# Charger_Board.net
KiCad netlist of a schematic drawn in EAGLE
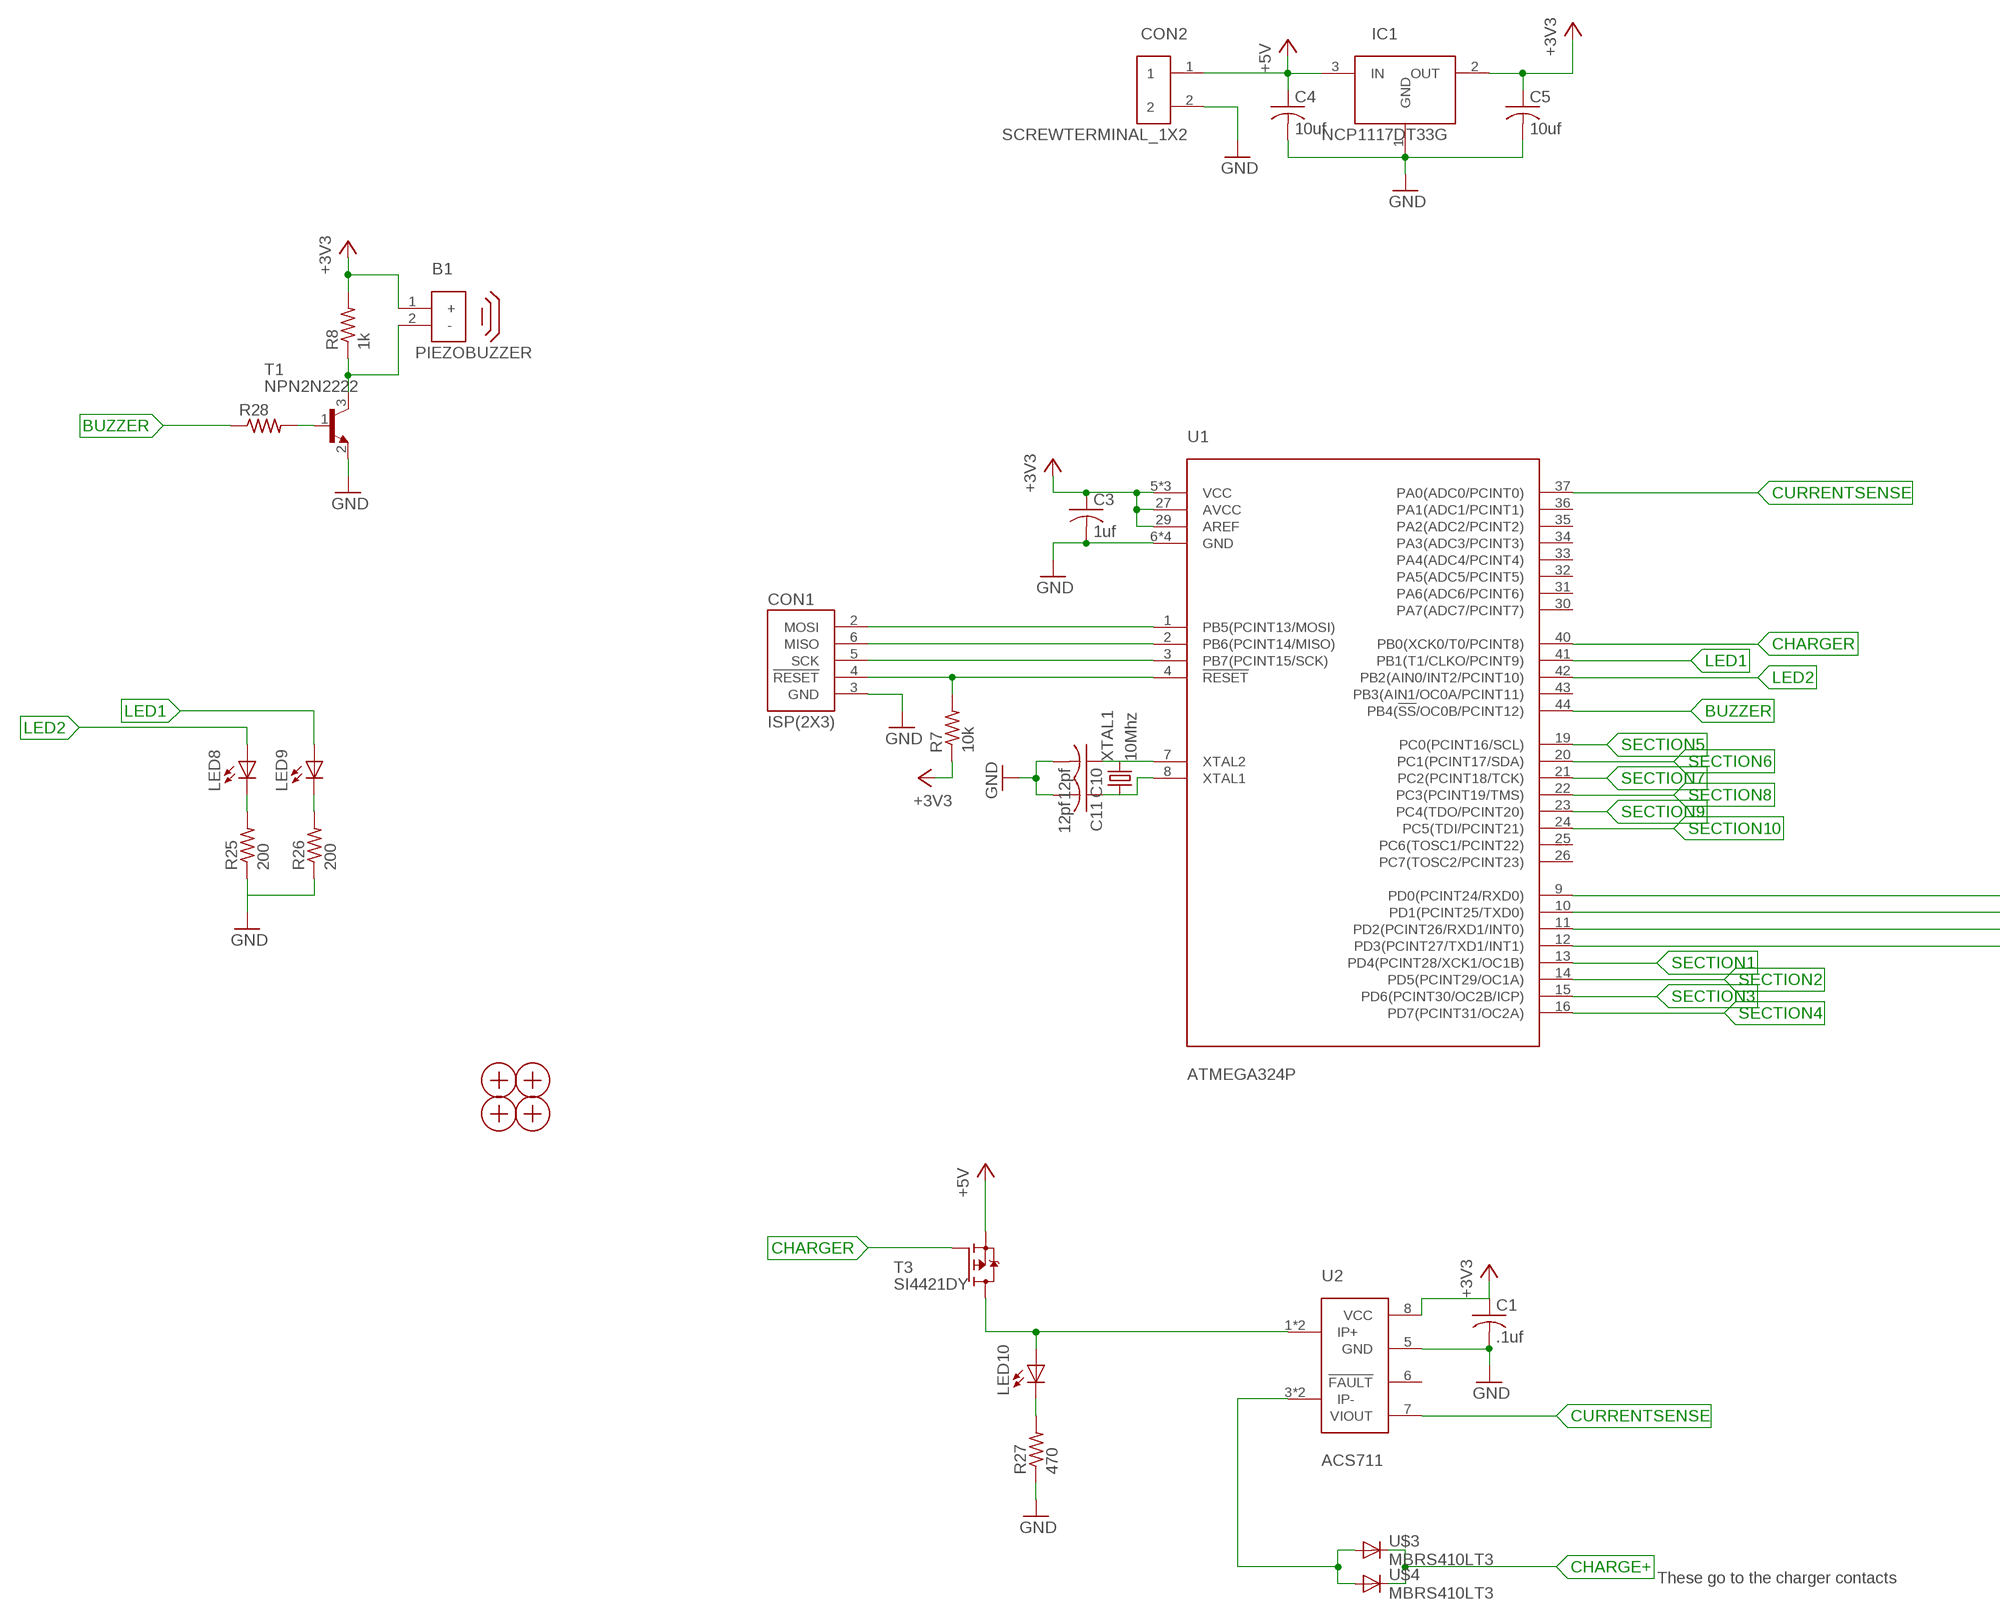
[diagram p0: schematic, sheet 1, part 1 of 2]
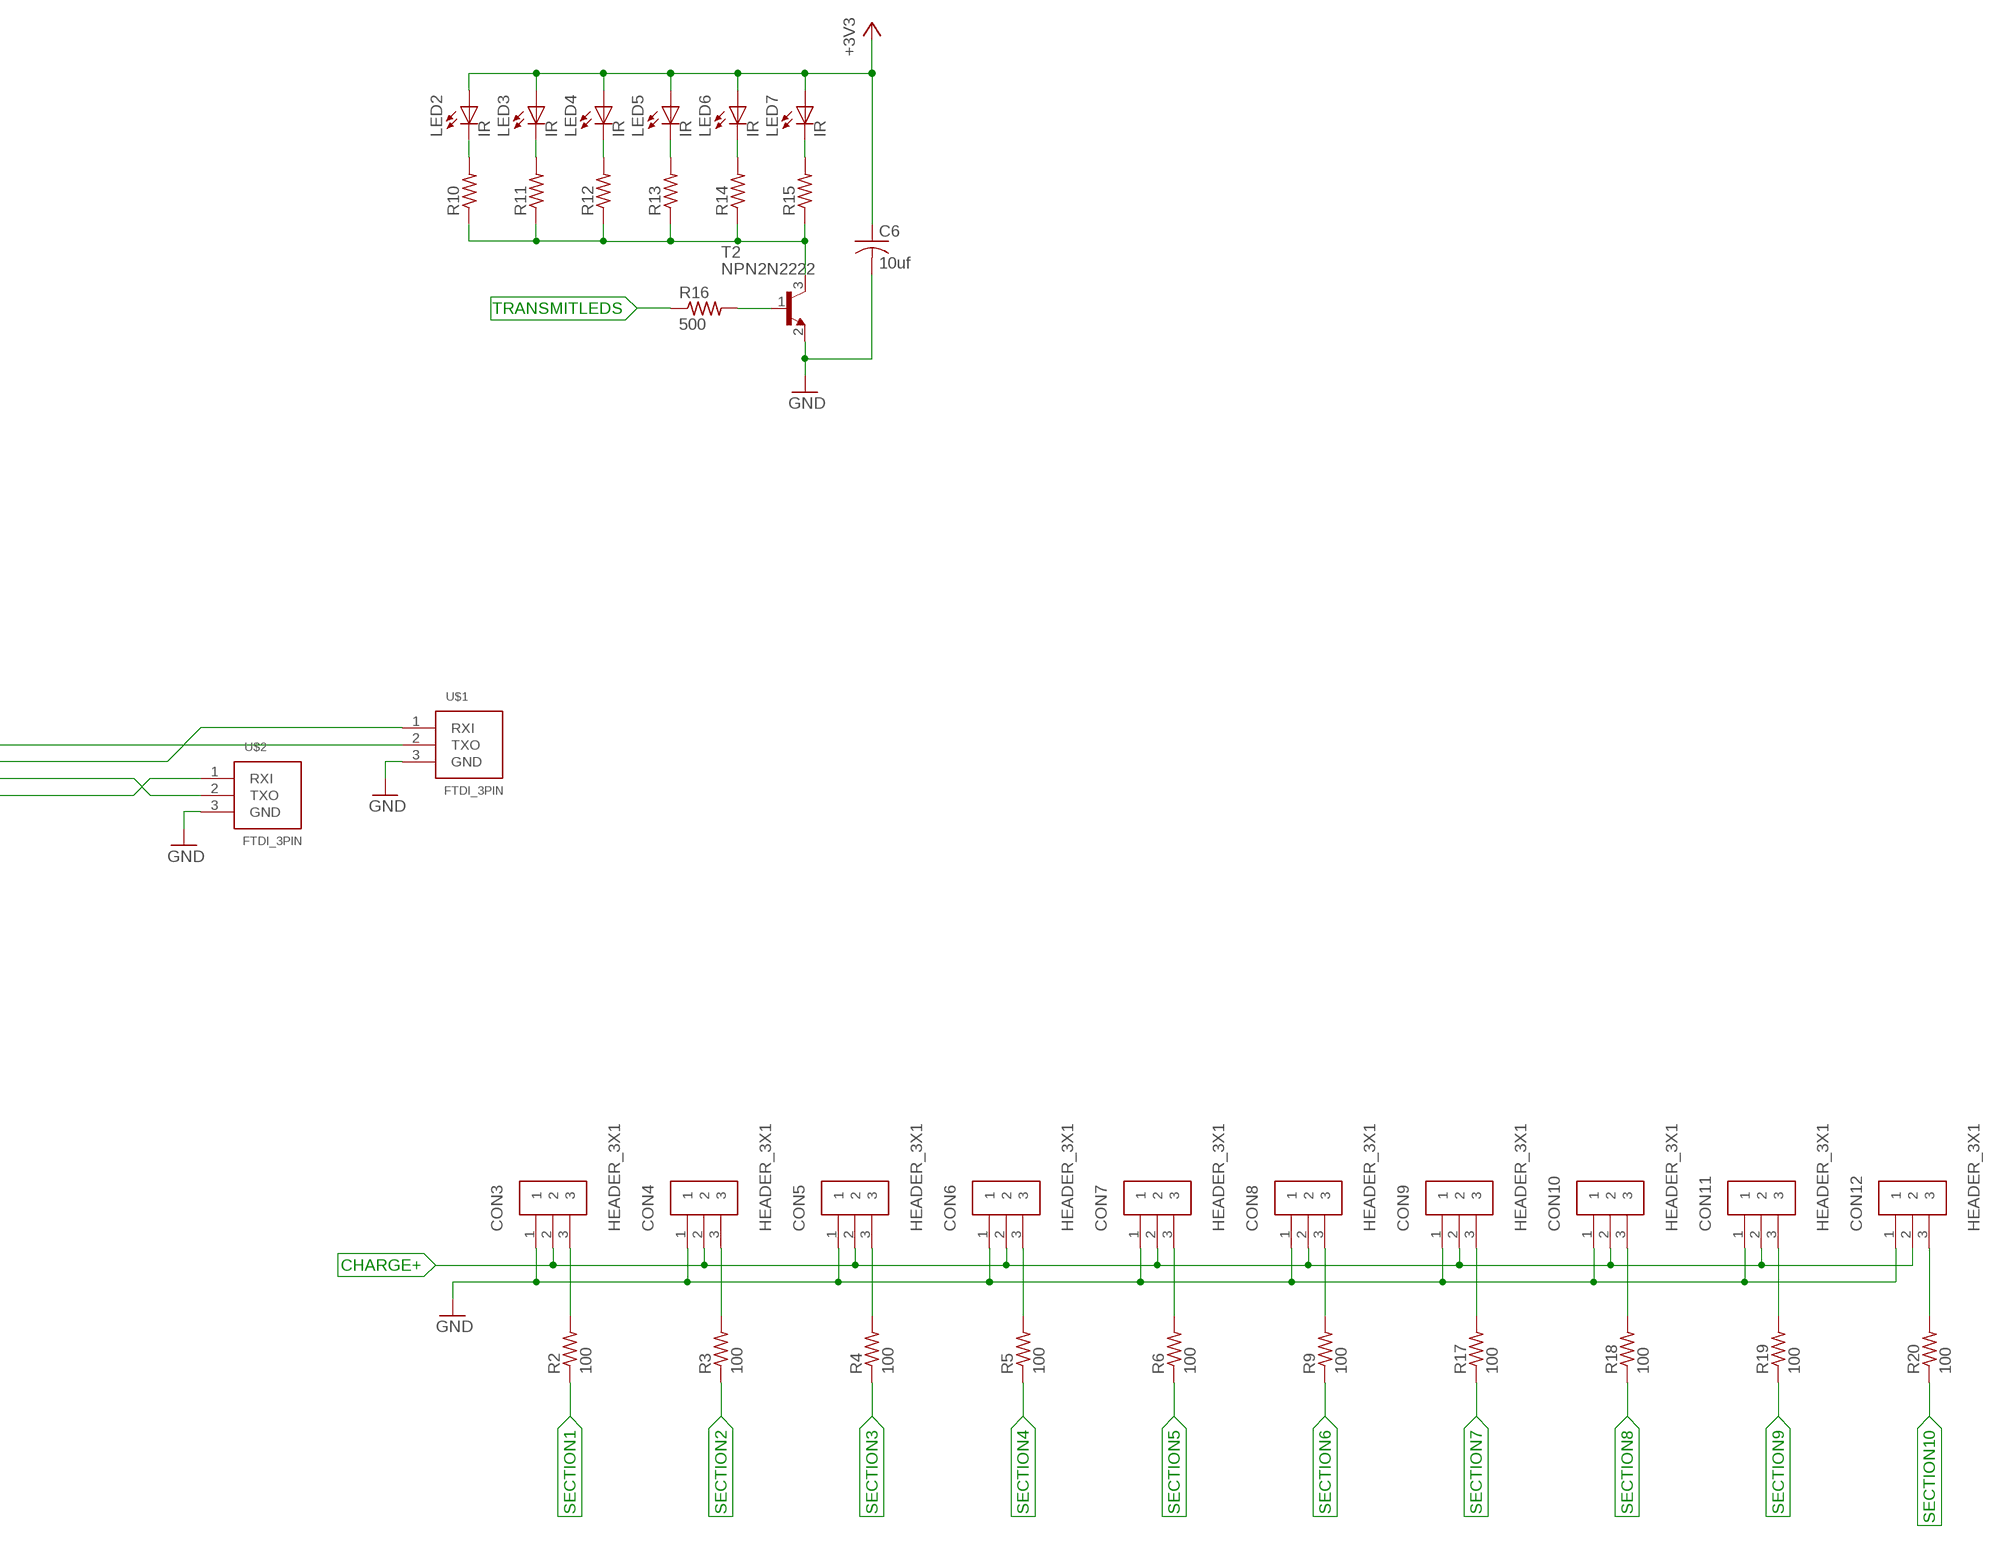
[diagram p1: schematic, sheet 1, part 2 of 2]

(export (version "E")
  (design (tool "Eeschema 10.0.6"))
  (components
    (comp (ref "B1")
      (value "PIEZOBUZZER")
      (footprint "eagle-import:PIEZOBUZZER")
      (libsource (lib "eagle-import") (part "PIEZOBUZZER"))
    )
    (comp (ref "C1")
      (value ".1uf")
      (footprint "eagle-import:0603")
      (libsource (lib "eagle-import") (part "CAP0603"))
    )
    (comp (ref "C3")
      (value "1uf")
      (footprint "eagle-import:0603")
      (libsource (lib "eagle-import") (part "CAP0603"))
    )
    (comp (ref "C4")
      (value "10uf")
      (footprint "eagle-import:0805")
      (libsource (lib "eagle-import") (part "CAP0805"))
    )
    (comp (ref "C5")
      (value "10uf")
      (footprint "eagle-import:0805")
      (libsource (lib "eagle-import") (part "CAP0805"))
    )
    (comp (ref "C6")
      (value "10uf")
      (footprint "eagle-import:0805")
      (libsource (lib "eagle-import") (part "CAP0805"))
    )
    (comp (ref "C10")
      (value "12pf")
      (footprint "eagle-import:0603")
      (libsource (lib "eagle-import") (part "CAP0603"))
    )
    (comp (ref "C11")
      (value "12pf")
      (footprint "eagle-import:0603")
      (libsource (lib "eagle-import") (part "CAP0603"))
    )
    (comp (ref "CON1")
      (value "ISP(2X3)")
      (footprint "eagle-import:PINHEADER(2X3)")
      (libsource (lib "eagle-import") (part "ISP(2X3)"))
    )
    (comp (ref "CON2")
      (value "SCREWTERMINAL_1X2")
      (footprint "eagle-import:SCREWTERMINAL_1X2")
      (libsource (lib "eagle-import") (part "SCREWTERMINAL_1X2"))
    )
    (comp (ref "CON3")
      (value "HEADER_3X1")
      (footprint "eagle-import:3PINHEADER_.100_")
      (libsource (lib "eagle-import") (part "HEADER_3X1"))
    )
    (comp (ref "CON4")
      (value "HEADER_3X1")
      (footprint "eagle-import:3PINHEADER_.100_")
      (libsource (lib "eagle-import") (part "HEADER_3X1"))
    )
    (comp (ref "CON5")
      (value "HEADER_3X1")
      (footprint "eagle-import:3PINHEADER_.100_")
      (libsource (lib "eagle-import") (part "HEADER_3X1"))
    )
    (comp (ref "CON6")
      (value "HEADER_3X1")
      (footprint "eagle-import:3PINHEADER_.100_")
      (libsource (lib "eagle-import") (part "HEADER_3X1"))
    )
    (comp (ref "CON7")
      (value "HEADER_3X1")
      (footprint "eagle-import:3PINHEADER_.100_")
      (libsource (lib "eagle-import") (part "HEADER_3X1"))
    )
    (comp (ref "CON8")
      (value "HEADER_3X1")
      (footprint "eagle-import:3PINHEADER_.100_")
      (libsource (lib "eagle-import") (part "HEADER_3X1"))
    )
    (comp (ref "CON9")
      (value "HEADER_3X1")
      (footprint "eagle-import:3PINHEADER_.100_")
      (libsource (lib "eagle-import") (part "HEADER_3X1"))
    )
    (comp (ref "CON10")
      (value "HEADER_3X1")
      (footprint "eagle-import:3PINHEADER_.100_")
      (libsource (lib "eagle-import") (part "HEADER_3X1"))
    )
    (comp (ref "CON11")
      (value "HEADER_3X1")
      (footprint "eagle-import:3PINHEADER_.100_")
      (libsource (lib "eagle-import") (part "HEADER_3X1"))
    )
    (comp (ref "CON12")
      (value "HEADER_3X1")
      (footprint "eagle-import:3PINHEADER_.100_")
      (libsource (lib "eagle-import") (part "HEADER_3X1"))
    )
    (comp (ref "H1")
      (value "MOUNTINGHOLE")
      (footprint "eagle-import:MOUNTINGHOLE")
      (libsource (lib "eagle-import") (part "MOUNTINGHOLE"))
    )
    (comp (ref "H2")
      (value "MOUNTINGHOLE")
      (footprint "eagle-import:MOUNTINGHOLE")
      (libsource (lib "eagle-import") (part "MOUNTINGHOLE"))
    )
    (comp (ref "H3")
      (value "MOUNTINGHOLE")
      (footprint "eagle-import:MOUNTINGHOLE")
      (libsource (lib "eagle-import") (part "MOUNTINGHOLE"))
    )
    (comp (ref "H4")
      (value "MOUNTINGHOLE")
      (footprint "eagle-import:MOUNTINGHOLE")
      (libsource (lib "eagle-import") (part "MOUNTINGHOLE"))
    )
    (comp (ref "IC1")
      (value "NCP1117DT33G")
      (footprint "eagle-import:DPAK")
      (libsource (lib "eagle-import") (part "NCP1117DT33G"))
    )
    (comp (ref "LED2")
      (value "IR")
      (footprint "eagle-import:5MM_LED_RA")
      (libsource (lib "eagle-import") (part "LED5MMRA"))
    )
    (comp (ref "LED3")
      (value "IR")
      (footprint "eagle-import:5MM_LED_RA")
      (libsource (lib "eagle-import") (part "LED5MMRA"))
    )
    (comp (ref "LED4")
      (value "IR")
      (footprint "eagle-import:5MM_LED_RA")
      (libsource (lib "eagle-import") (part "LED5MMRA"))
    )
    (comp (ref "LED5")
      (value "IR")
      (footprint "eagle-import:5MM_LED_RA")
      (libsource (lib "eagle-import") (part "LED5MMRA"))
    )
    (comp (ref "LED6")
      (value "IR")
      (footprint "eagle-import:5MM_LED_RA")
      (libsource (lib "eagle-import") (part "LED5MMRA"))
    )
    (comp (ref "LED7")
      (value "IR")
      (footprint "eagle-import:5MM_LED_RA")
      (libsource (lib "eagle-import") (part "LED5MMRA"))
    )
    (comp (ref "LED8")
      (value "LED0603")
      (footprint "eagle-import:LED0603")
      (libsource (lib "eagle-import") (part "LED0603"))
    )
    (comp (ref "LED9")
      (value "LED0603")
      (footprint "eagle-import:LED0603")
      (libsource (lib "eagle-import") (part "LED0603"))
    )
    (comp (ref "LED10")
      (value "LED0603")
      (footprint "eagle-import:LED0603")
      (libsource (lib "eagle-import") (part "LED0603"))
    )
    (comp (ref "R2")
      (value "100")
      (footprint "eagle-import:0603")
      (libsource (lib "eagle-import") (part "RES0603"))
    )
    (comp (ref "R3")
      (value "100")
      (footprint "eagle-import:0603")
      (libsource (lib "eagle-import") (part "RES0603"))
    )
    (comp (ref "R4")
      (value "100")
      (footprint "eagle-import:0603")
      (libsource (lib "eagle-import") (part "RES0603"))
    )
    (comp (ref "R5")
      (value "100")
      (footprint "eagle-import:0603")
      (libsource (lib "eagle-import") (part "RES0603"))
    )
    (comp (ref "R6")
      (value "100")
      (footprint "eagle-import:0603")
      (libsource (lib "eagle-import") (part "RES0603"))
    )
    (comp (ref "R7")
      (value "10k")
      (footprint "eagle-import:0603")
      (libsource (lib "eagle-import") (part "RES0603"))
    )
    (comp (ref "R8")
      (value "1k")
      (footprint "eagle-import:0603")
      (libsource (lib "eagle-import") (part "RES0603"))
    )
    (comp (ref "R9")
      (value "100")
      (footprint "eagle-import:0603")
      (libsource (lib "eagle-import") (part "RES0603"))
    )
    (comp (ref "R10")
      (value "RES0603")
      (footprint "eagle-import:0603")
      (libsource (lib "eagle-import") (part "RES0603"))
    )
    (comp (ref "R11")
      (value "RES0603")
      (footprint "eagle-import:0603")
      (libsource (lib "eagle-import") (part "RES0603"))
    )
    (comp (ref "R12")
      (value "RES0603")
      (footprint "eagle-import:0603")
      (libsource (lib "eagle-import") (part "RES0603"))
    )
    (comp (ref "R13")
      (value "RES0603")
      (footprint "eagle-import:0603")
      (libsource (lib "eagle-import") (part "RES0603"))
    )
    (comp (ref "R14")
      (value "RES0603")
      (footprint "eagle-import:0603")
      (libsource (lib "eagle-import") (part "RES0603"))
    )
    (comp (ref "R15")
      (value "RES0603")
      (footprint "eagle-import:0603")
      (libsource (lib "eagle-import") (part "RES0603"))
    )
    (comp (ref "R16")
      (value "500")
      (footprint "eagle-import:0603")
      (libsource (lib "eagle-import") (part "RES0603"))
    )
    (comp (ref "R17")
      (value "100")
      (footprint "eagle-import:0603")
      (libsource (lib "eagle-import") (part "RES0603"))
    )
    (comp (ref "R18")
      (value "100")
      (footprint "eagle-import:0603")
      (libsource (lib "eagle-import") (part "RES0603"))
    )
    (comp (ref "R19")
      (value "100")
      (footprint "eagle-import:0603")
      (libsource (lib "eagle-import") (part "RES0603"))
    )
    (comp (ref "R20")
      (value "100")
      (footprint "eagle-import:0603")
      (libsource (lib "eagle-import") (part "RES0603"))
    )
    (comp (ref "R25")
      (value "200")
      (footprint "eagle-import:0603")
      (libsource (lib "eagle-import") (part "RES0603"))
    )
    (comp (ref "R26")
      (value "200")
      (footprint "eagle-import:0603")
      (libsource (lib "eagle-import") (part "RES0603"))
    )
    (comp (ref "R27")
      (value "470")
      (footprint "eagle-import:0603")
      (libsource (lib "eagle-import") (part "RES0603"))
    )
    (comp (ref "R28")
      (value "RES0603")
      (footprint "eagle-import:0603")
      (libsource (lib "eagle-import") (part "RES0603"))
    )
    (comp (ref "T1")
      (value "NPN2N2222")
      (footprint "eagle-import:SOT23")
      (libsource (lib "eagle-import") (part "NPN2N2222"))
    )
    (comp (ref "T2")
      (value "NPN2N2222")
      (footprint "eagle-import:SOT23")
      (libsource (lib "eagle-import") (part "NPN2N2222"))
    )
    (comp (ref "T3")
      (value "SI4421DY")
      (footprint "eagle-import:S0-8")
      (libsource (lib "eagle-import") (part "SI4421DY"))
    )
    (comp (ref "U$1")
      (value "FTDI_3PIN")
      (footprint "eagle-import:3PINHEADER_.100_")
      (libsource (lib "eagle-import") (part "FTDI_3PIN"))
    )
    (comp (ref "U$2")
      (value "FTDI_3PIN")
      (footprint "eagle-import:3PINHEADER_.100_")
      (libsource (lib "eagle-import") (part "FTDI_3PIN"))
    )
    (comp (ref "U$3")
      (value "MBRS410LT3")
      (footprint "eagle-import:SMD_DIODE")
      (libsource (lib "eagle-import") (part "MBRS410LT3"))
    )
    (comp (ref "U$4")
      (value "MBRS410LT3")
      (footprint "eagle-import:SMD_DIODE")
      (libsource (lib "eagle-import") (part "MBRS410LT3"))
    )
    (comp (ref "U1")
      (value "ATMEGA324P")
      (footprint "eagle-import:TQFP44")
      (libsource (lib "eagle-import") (part "ATMEGA324P"))
    )
    (comp (ref "U2")
      (value "ACS711")
      (footprint "eagle-import:8SOIC")
      (libsource (lib "eagle-import") (part "ACS711"))
    )
    (comp (ref "XTAL1")
      (value "10Mhz")
      (footprint "eagle-import:SMDXTAL")
      (libsource (lib "eagle-import") (part "NX5032GA-10.000000MHZ"))
    )
  )
  (nets
    (net (code "1") (name "+3V3") (class "Default")
      (node (ref "B1") (pin "1") (pinfunction "+_1") (pintype "bidirectional"))
      (node (ref "C1") (pin "1") (pinfunction "1_1") (pintype "passive"))
      (node (ref "C3") (pin "1") (pinfunction "1_1") (pintype "passive"))
      (node (ref "C5") (pin "1") (pinfunction "1_1") (pintype "passive"))
      (node (ref "C6") (pin "1") (pinfunction "1_1") (pintype "passive"))
      (node (ref "IC1") (pin "2") (pinfunction "OUT_2") (pintype "bidirectional"))
      (node (ref "LED2") (pin "1") (pinfunction "A_1") (pintype "passive"))
      (node (ref "LED3") (pin "1") (pinfunction "A_1") (pintype "passive"))
      (node (ref "LED4") (pin "1") (pinfunction "A_1") (pintype "passive"))
      (node (ref "LED5") (pin "1") (pinfunction "A_1") (pintype "passive"))
      (node (ref "LED6") (pin "1") (pinfunction "A_1") (pintype "passive"))
      (node (ref "LED7") (pin "1") (pinfunction "A_1") (pintype "passive"))
      (node (ref "R7") (pin "1") (pinfunction "1_1") (pintype "passive"))
      (node (ref "R8") (pin "2") (pinfunction "2_2") (pintype "passive"))
      (node (ref "U1") (pin "17") (pinfunction "VCC_17") (pintype "bidirectional"))
      (node (ref "U1") (pin "27") (pinfunction "AVCC_27") (pintype "bidirectional"))
      (node (ref "U1") (pin "29") (pinfunction "AREF_29") (pintype "bidirectional"))
      (node (ref "U1") (pin "38") (pinfunction "VCC_38") (pintype "bidirectional"))
      (node (ref "U1") (pin "5") (pinfunction "VCC_5") (pintype "bidirectional"))
      (node (ref "U2") (pin "8") (pinfunction "VCC_8") (pintype "bidirectional"))
    )
    (net (code "2") (name "+5V") (class "Default")
      (node (ref "C4") (pin "1") (pinfunction "1_1") (pintype "passive"))
      (node (ref "CON2") (pin "1") (pinfunction "1_1") (pintype "bidirectional"))
      (node (ref "IC1") (pin "3") (pinfunction "IN_3") (pintype "bidirectional"))
      (node (ref "T3") (pin "1") (pinfunction "S_1") (pintype "passive"))
      (node (ref "T3") (pin "2") (pinfunction "S_2") (pintype "passive"))
      (node (ref "T3") (pin "3") (pinfunction "S_3") (pintype "passive"))
    )
    (net (code "3") (name "BUZZER") (class "Default")
      (node (ref "R28") (pin "1") (pinfunction "1_1") (pintype "passive"))
      (node (ref "U1") (pin "44") (pinfunction "PB4(~{SS}/OC0B/PCINT12)_44") (pintype "bidirectional"))
    )
    (net (code "4") (name "CHARGE+") (class "Default")
      (node (ref "CON10") (pin "2") (pinfunction "2_2") (pintype "bidirectional"))
      (node (ref "CON11") (pin "2") (pinfunction "2_2") (pintype "bidirectional"))
      (node (ref "CON12") (pin "2") (pinfunction "2_2") (pintype "bidirectional"))
      (node (ref "CON3") (pin "2") (pinfunction "2_2") (pintype "bidirectional"))
      (node (ref "CON4") (pin "2") (pinfunction "2_2") (pintype "bidirectional"))
      (node (ref "CON5") (pin "2") (pinfunction "2_2") (pintype "bidirectional"))
      (node (ref "CON6") (pin "2") (pinfunction "2_2") (pintype "bidirectional"))
      (node (ref "CON7") (pin "2") (pinfunction "2_2") (pintype "bidirectional"))
      (node (ref "CON8") (pin "2") (pinfunction "2_2") (pintype "bidirectional"))
      (node (ref "CON9") (pin "2") (pinfunction "2_2") (pintype "bidirectional"))
      (node (ref "U$3") (pin "2") (pinfunction "C_2") (pintype "passive"))
      (node (ref "U$4") (pin "2") (pinfunction "C_2") (pintype "passive"))
    )
    (net (code "5") (name "CHARGER") (class "Default")
      (node (ref "T3") (pin "4") (pinfunction "G_4") (pintype "passive"))
      (node (ref "U1") (pin "40") (pinfunction "PB0(XCK0/T0/PCINT8)_40") (pintype "bidirectional"))
    )
    (net (code "6") (name "CURRENTSENSE") (class "Default")
      (node (ref "U1") (pin "37") (pinfunction "PA0(ADC0/PCINT0)_37") (pintype "bidirectional"))
      (node (ref "U2") (pin "7") (pinfunction "VIOUT_7") (pintype "bidirectional"))
    )
    (net (code "7") (name "GND") (class "Default")
      (node (ref "C1") (pin "2") (pinfunction "2_2") (pintype "passive"))
      (node (ref "C10") (pin "2") (pinfunction "2_2") (pintype "passive"))
      (node (ref "C11") (pin "2") (pinfunction "2_2") (pintype "passive"))
      (node (ref "C3") (pin "2") (pinfunction "2_2") (pintype "passive"))
      (node (ref "C4") (pin "2") (pinfunction "2_2") (pintype "passive"))
      (node (ref "C5") (pin "2") (pinfunction "2_2") (pintype "passive"))
      (node (ref "C6") (pin "2") (pinfunction "2_2") (pintype "passive"))
      (node (ref "CON1") (pin "3") (pinfunction "GND_3") (pintype "bidirectional"))
      (node (ref "CON10") (pin "1") (pinfunction "1_1") (pintype "bidirectional"))
      (node (ref "CON11") (pin "1") (pinfunction "1_1") (pintype "bidirectional"))
      (node (ref "CON12") (pin "1") (pinfunction "1_1") (pintype "bidirectional"))
      (node (ref "CON2") (pin "2") (pinfunction "2_2") (pintype "bidirectional"))
      (node (ref "CON3") (pin "1") (pinfunction "1_1") (pintype "bidirectional"))
      (node (ref "CON4") (pin "1") (pinfunction "1_1") (pintype "bidirectional"))
      (node (ref "CON5") (pin "1") (pinfunction "1_1") (pintype "bidirectional"))
      (node (ref "CON6") (pin "1") (pinfunction "1_1") (pintype "bidirectional"))
      (node (ref "CON7") (pin "1") (pinfunction "1_1") (pintype "bidirectional"))
      (node (ref "CON8") (pin "1") (pinfunction "1_1") (pintype "bidirectional"))
      (node (ref "CON9") (pin "1") (pinfunction "1_1") (pintype "bidirectional"))
      (node (ref "IC1") (pin "1") (pinfunction "GND_1") (pintype "bidirectional"))
      (node (ref "R25") (pin "1") (pinfunction "1_1") (pintype "passive"))
      (node (ref "R26") (pin "1") (pinfunction "1_1") (pintype "passive"))
      (node (ref "R27") (pin "1") (pinfunction "1_1") (pintype "passive"))
      (node (ref "T1") (pin "2") (pinfunction "E_2") (pintype "passive"))
      (node (ref "T2") (pin "2") (pinfunction "E_2") (pintype "passive"))
      (node (ref "U$1") (pin "3") (pinfunction "GND_3") (pintype "bidirectional"))
      (node (ref "U$2") (pin "3") (pinfunction "GND_3") (pintype "bidirectional"))
      (node (ref "U1") (pin "18") (pinfunction "GND_18") (pintype "bidirectional"))
      (node (ref "U1") (pin "28") (pinfunction "GND_28") (pintype "bidirectional"))
      (node (ref "U1") (pin "39") (pinfunction "GND_39") (pintype "bidirectional"))
      (node (ref "U1") (pin "6") (pinfunction "GND_6") (pintype "bidirectional"))
      (node (ref "U2") (pin "5") (pinfunction "GND_5") (pintype "bidirectional"))
    )
    (net (code "8") (name "LED1") (class "Default")
      (node (ref "LED9") (pin "2") (pinfunction "A_2") (pintype "passive"))
      (node (ref "U1") (pin "41") (pinfunction "PB1(T1/CLKO/PCINT9)_41") (pintype "bidirectional"))
    )
    (net (code "9") (name "LED2") (class "Default")
      (node (ref "LED8") (pin "2") (pinfunction "A_2") (pintype "passive"))
      (node (ref "U1") (pin "42") (pinfunction "PB2(AIN0/INT2/PCINT10)_42") (pintype "bidirectional"))
    )
    (net (code "10") (name "Net-(B1--)") (class "Default")
      (node (ref "B1") (pin "2") (pinfunction "-_2") (pintype "bidirectional"))
      (node (ref "R8") (pin "1") (pinfunction "1_1") (pintype "passive"))
      (node (ref "T1") (pin "3") (pinfunction "C_3") (pintype "passive"))
    )
    (net (code "11") (name "Net-(CON1-MISO)") (class "Default")
      (node (ref "CON1") (pin "6") (pinfunction "MISO_6") (pintype "bidirectional"))
      (node (ref "U1") (pin "2") (pinfunction "PB6(PCINT14/MISO)_2") (pintype "bidirectional"))
    )
    (net (code "12") (name "Net-(CON1-MOSI)") (class "Default")
      (node (ref "CON1") (pin "2") (pinfunction "MOSI_2") (pintype "bidirectional"))
      (node (ref "U1") (pin "1") (pinfunction "PB5(PCINT13/MOSI)_1") (pintype "bidirectional"))
    )
    (net (code "13") (name "Net-(CON1-SCK)") (class "Default")
      (node (ref "CON1") (pin "5") (pinfunction "SCK_5") (pintype "bidirectional"))
      (node (ref "U1") (pin "3") (pinfunction "PB7(PCINT15/SCK)_3") (pintype "bidirectional"))
    )
    (net (code "14") (name "Net-(CON1-~{RESET})") (class "Default")
      (node (ref "CON1") (pin "4") (pinfunction "~{RESET}_4") (pintype "bidirectional"))
      (node (ref "R7") (pin "2") (pinfunction "2_2") (pintype "passive"))
      (node (ref "U1") (pin "4") (pinfunction "~{RESET}_4") (pintype "bidirectional"))
    )
    (net (code "15") (name "Net-(CON3-Pad3)") (class "Default")
      (node (ref "CON3") (pin "3") (pinfunction "3_3") (pintype "bidirectional"))
      (node (ref "R2") (pin "2") (pinfunction "2_2") (pintype "passive"))
    )
    (net (code "16") (name "Net-(CON4-Pad3)") (class "Default")
      (node (ref "CON4") (pin "3") (pinfunction "3_3") (pintype "bidirectional"))
      (node (ref "R3") (pin "2") (pinfunction "2_2") (pintype "passive"))
    )
    (net (code "17") (name "Net-(CON5-Pad3)") (class "Default")
      (node (ref "CON5") (pin "3") (pinfunction "3_3") (pintype "bidirectional"))
      (node (ref "R4") (pin "2") (pinfunction "2_2") (pintype "passive"))
    )
    (net (code "18") (name "Net-(CON6-Pad3)") (class "Default")
      (node (ref "CON6") (pin "3") (pinfunction "3_3") (pintype "bidirectional"))
      (node (ref "R5") (pin "2") (pinfunction "2_2") (pintype "passive"))
    )
    (net (code "19") (name "Net-(CON7-Pad3)") (class "Default")
      (node (ref "CON7") (pin "3") (pinfunction "3_3") (pintype "bidirectional"))
      (node (ref "R6") (pin "2") (pinfunction "2_2") (pintype "passive"))
    )
    (net (code "20") (name "Net-(CON8-Pad3)") (class "Default")
      (node (ref "CON8") (pin "3") (pinfunction "3_3") (pintype "bidirectional"))
      (node (ref "R9") (pin "2") (pinfunction "2_2") (pintype "passive"))
    )
    (net (code "21") (name "Net-(CON9-Pad3)") (class "Default")
      (node (ref "CON9") (pin "3") (pinfunction "3_3") (pintype "bidirectional"))
      (node (ref "R17") (pin "2") (pinfunction "2_2") (pintype "passive"))
    )
    (net (code "22") (name "Net-(CON10-Pad3)") (class "Default")
      (node (ref "CON10") (pin "3") (pinfunction "3_3") (pintype "bidirectional"))
      (node (ref "R18") (pin "2") (pinfunction "2_2") (pintype "passive"))
    )
    (net (code "23") (name "Net-(CON11-Pad3)") (class "Default")
      (node (ref "CON11") (pin "3") (pinfunction "3_3") (pintype "bidirectional"))
      (node (ref "R19") (pin "2") (pinfunction "2_2") (pintype "passive"))
    )
    (net (code "24") (name "Net-(CON12-Pad3)") (class "Default")
      (node (ref "CON12") (pin "3") (pinfunction "3_3") (pintype "bidirectional"))
      (node (ref "R20") (pin "2") (pinfunction "2_2") (pintype "passive"))
    )
    (net (code "25") (name "Net-(LED2-C)") (class "Default")
      (node (ref "LED2") (pin "2") (pinfunction "C_2") (pintype "passive"))
      (node (ref "R10") (pin "2") (pinfunction "2_2") (pintype "passive"))
    )
    (net (code "26") (name "Net-(LED3-C)") (class "Default")
      (node (ref "LED3") (pin "2") (pinfunction "C_2") (pintype "passive"))
      (node (ref "R11") (pin "2") (pinfunction "2_2") (pintype "passive"))
    )
    (net (code "27") (name "Net-(LED4-C)") (class "Default")
      (node (ref "LED4") (pin "2") (pinfunction "C_2") (pintype "passive"))
      (node (ref "R12") (pin "2") (pinfunction "2_2") (pintype "passive"))
    )
    (net (code "28") (name "Net-(LED5-C)") (class "Default")
      (node (ref "LED5") (pin "2") (pinfunction "C_2") (pintype "passive"))
      (node (ref "R13") (pin "2") (pinfunction "2_2") (pintype "passive"))
    )
    (net (code "29") (name "Net-(LED6-C)") (class "Default")
      (node (ref "LED6") (pin "2") (pinfunction "C_2") (pintype "passive"))
      (node (ref "R14") (pin "2") (pinfunction "2_2") (pintype "passive"))
    )
    (net (code "30") (name "Net-(LED7-C)") (class "Default")
      (node (ref "LED7") (pin "2") (pinfunction "C_2") (pintype "passive"))
      (node (ref "R15") (pin "2") (pinfunction "2_2") (pintype "passive"))
    )
    (net (code "31") (name "Net-(LED8-C)") (class "Default")
      (node (ref "LED8") (pin "1") (pinfunction "C_1") (pintype "passive"))
      (node (ref "R25") (pin "2") (pinfunction "2_2") (pintype "passive"))
    )
    (net (code "32") (name "Net-(LED9-C)") (class "Default")
      (node (ref "LED9") (pin "1") (pinfunction "C_1") (pintype "passive"))
      (node (ref "R26") (pin "2") (pinfunction "2_2") (pintype "passive"))
    )
    (net (code "33") (name "Net-(LED10-A)") (class "Default")
      (node (ref "LED10") (pin "2") (pinfunction "A_2") (pintype "passive"))
      (node (ref "T3") (pin "5") (pinfunction "D_5") (pintype "passive"))
      (node (ref "T3") (pin "6") (pinfunction "D_6") (pintype "passive"))
      (node (ref "T3") (pin "7") (pinfunction "D_7") (pintype "passive"))
      (node (ref "T3") (pin "8") (pinfunction "D_8") (pintype "passive"))
      (node (ref "U2") (pin "1") (pinfunction "IP+_1") (pintype "bidirectional"))
      (node (ref "U2") (pin "2") (pinfunction "IP+_2") (pintype "bidirectional"))
    )
    (net (code "34") (name "Net-(LED10-C)") (class "Default")
      (node (ref "LED10") (pin "1") (pinfunction "C_1") (pintype "passive"))
      (node (ref "R27") (pin "2") (pinfunction "2_2") (pintype "passive"))
    )
    (net (code "35") (name "Net-(T1-B)") (class "Default")
      (node (ref "R28") (pin "2") (pinfunction "2_2") (pintype "passive"))
      (node (ref "T1") (pin "1") (pinfunction "B_1") (pintype "passive"))
    )
    (net (code "36") (name "Net-(T2-B)") (class "Default")
      (node (ref "R16") (pin "2") (pinfunction "2_2") (pintype "passive"))
      (node (ref "T2") (pin "1") (pinfunction "B_1") (pintype "passive"))
    )
    (net (code "37") (name "Net-(T2-C)") (class "Default")
      (node (ref "R10") (pin "1") (pinfunction "1_1") (pintype "passive"))
      (node (ref "R11") (pin "1") (pinfunction "1_1") (pintype "passive"))
      (node (ref "R12") (pin "1") (pinfunction "1_1") (pintype "passive"))
      (node (ref "R13") (pin "1") (pinfunction "1_1") (pintype "passive"))
      (node (ref "R14") (pin "1") (pinfunction "1_1") (pintype "passive"))
      (node (ref "R15") (pin "1") (pinfunction "1_1") (pintype "passive"))
      (node (ref "T2") (pin "3") (pinfunction "C_3") (pintype "passive"))
    )
    (net (code "38") (name "Net-(U$1-RXI)") (class "Default")
      (node (ref "U$1") (pin "1") (pinfunction "RXI_1") (pintype "bidirectional"))
      (node (ref "U1") (pin "10") (pinfunction "PD1(PCINT25/TXD0)_10") (pintype "bidirectional"))
    )
    (net (code "39") (name "Net-(U$1-TXO)") (class "Default")
      (node (ref "U$1") (pin "2") (pinfunction "TXO_2") (pintype "bidirectional"))
      (node (ref "U1") (pin "9") (pinfunction "PD0(PCINT24/RXD0)_9") (pintype "bidirectional"))
    )
    (net (code "40") (name "Net-(U$2-RXI)") (class "Default")
      (node (ref "U$2") (pin "1") (pinfunction "RXI_1") (pintype "bidirectional"))
      (node (ref "U1") (pin "12") (pinfunction "PD3(PCINT27/TXD1/INT1)_12") (pintype "bidirectional"))
    )
    (net (code "41") (name "Net-(U$2-TXO)") (class "Default")
      (node (ref "U$2") (pin "2") (pinfunction "TXO_2") (pintype "bidirectional"))
      (node (ref "U1") (pin "11") (pinfunction "PD2(PCINT26/RXD1/INT0)_11") (pintype "bidirectional"))
    )
    (net (code "42") (name "Net-(U$3-A)") (class "Default")
      (node (ref "U$3") (pin "1") (pinfunction "A_1") (pintype "passive"))
      (node (ref "U$4") (pin "1") (pinfunction "A_1") (pintype "passive"))
      (node (ref "U2") (pin "3") (pinfunction "IP-_3") (pintype "bidirectional"))
      (node (ref "U2") (pin "4") (pinfunction "IP-_4") (pintype "bidirectional"))
    )
    (net (code "43") (name "Net-(U1-XTAL1)") (class "Default")
      (node (ref "C11") (pin "1") (pinfunction "1_1") (pintype "passive"))
      (node (ref "U1") (pin "8") (pinfunction "XTAL1_8") (pintype "bidirectional"))
      (node (ref "XTAL1") (pin "1") (pinfunction "1_1") (pintype "passive"))
    )
    (net (code "44") (name "Net-(U1-XTAL2)") (class "Default")
      (node (ref "C10") (pin "1") (pinfunction "1_1") (pintype "passive"))
      (node (ref "U1") (pin "7") (pinfunction "XTAL2_7") (pintype "bidirectional"))
      (node (ref "XTAL1") (pin "2") (pinfunction "2_2") (pintype "passive"))
    )
    (net (code "45") (name "SECTION1") (class "Default")
      (node (ref "R2") (pin "1") (pinfunction "1_1") (pintype "passive"))
      (node (ref "U1") (pin "13") (pinfunction "PD4(PCINT28/XCK1/OC1B)_13") (pintype "bidirectional"))
    )
    (net (code "46") (name "SECTION2") (class "Default")
      (node (ref "R3") (pin "1") (pinfunction "1_1") (pintype "passive"))
      (node (ref "U1") (pin "14") (pinfunction "PD5(PCINT29/OC1A)_14") (pintype "bidirectional"))
    )
    (net (code "47") (name "SECTION3") (class "Default")
      (node (ref "R4") (pin "1") (pinfunction "1_1") (pintype "passive"))
      (node (ref "U1") (pin "15") (pinfunction "PD6(PCINT30/OC2B/ICP)_15") (pintype "bidirectional"))
    )
    (net (code "48") (name "SECTION4") (class "Default")
      (node (ref "R5") (pin "1") (pinfunction "1_1") (pintype "passive"))
      (node (ref "U1") (pin "16") (pinfunction "PD7(PCINT31/OC2A)_16") (pintype "bidirectional"))
    )
    (net (code "49") (name "SECTION5") (class "Default")
      (node (ref "R6") (pin "1") (pinfunction "1_1") (pintype "passive"))
      (node (ref "U1") (pin "19") (pinfunction "PC0(PCINT16/SCL)_19") (pintype "bidirectional"))
    )
    (net (code "50") (name "SECTION6") (class "Default")
      (node (ref "R9") (pin "1") (pinfunction "1_1") (pintype "passive"))
      (node (ref "U1") (pin "20") (pinfunction "PC1(PCINT17/SDA)_20") (pintype "bidirectional"))
    )
    (net (code "51") (name "SECTION7") (class "Default")
      (node (ref "R17") (pin "1") (pinfunction "1_1") (pintype "passive"))
      (node (ref "U1") (pin "21") (pinfunction "PC2(PCINT18/TCK)_21") (pintype "bidirectional"))
    )
    (net (code "52") (name "SECTION8") (class "Default")
      (node (ref "R18") (pin "1") (pinfunction "1_1") (pintype "passive"))
      (node (ref "U1") (pin "22") (pinfunction "PC3(PCINT19/TMS)_22") (pintype "bidirectional"))
    )
    (net (code "53") (name "SECTION9") (class "Default")
      (node (ref "R19") (pin "1") (pinfunction "1_1") (pintype "passive"))
      (node (ref "U1") (pin "23") (pinfunction "PC4(TDO/PCINT20)_23") (pintype "bidirectional"))
    )
    (net (code "54") (name "SECTION10") (class "Default")
      (node (ref "R20") (pin "1") (pinfunction "1_1") (pintype "passive"))
      (node (ref "U1") (pin "24") (pinfunction "PC5(TDI/PCINT21)_24") (pintype "bidirectional"))
    )
    (net (code "55") (name "TRANSMITLEDS") (class "Default")
      (node (ref "R16") (pin "1") (pinfunction "1_1") (pintype "passive"))
    )
    (net (code "56") (name "unconnected-(U1-PA1(ADC1{slash}PCINT1)-Pad36)") (class "Default")
      (node (ref "U1") (pin "36") (pinfunction "PA1(ADC1/PCINT1)_36") (pintype "bidirectional"))
    )
    (net (code "57") (name "unconnected-(U1-PA2(ADC2{slash}PCINT2)-Pad35)") (class "Default")
      (node (ref "U1") (pin "35") (pinfunction "PA2(ADC2/PCINT2)_35") (pintype "bidirectional"))
    )
    (net (code "58") (name "unconnected-(U1-PA3(ADC3{slash}PCINT3)-Pad34)") (class "Default")
      (node (ref "U1") (pin "34") (pinfunction "PA3(ADC3/PCINT3)_34") (pintype "bidirectional"))
    )
    (net (code "59") (name "unconnected-(U1-PA4(ADC4{slash}PCINT4)-Pad33)") (class "Default")
      (node (ref "U1") (pin "33") (pinfunction "PA4(ADC4/PCINT4)_33") (pintype "bidirectional"))
    )
    (net (code "60") (name "unconnected-(U1-PA5(ADC5{slash}PCINT5)-Pad32)") (class "Default")
      (node (ref "U1") (pin "32") (pinfunction "PA5(ADC5/PCINT5)_32") (pintype "bidirectional"))
    )
    (net (code "61") (name "unconnected-(U1-PA6(ADC6{slash}PCINT6)-Pad31)") (class "Default")
      (node (ref "U1") (pin "31") (pinfunction "PA6(ADC6/PCINT6)_31") (pintype "bidirectional"))
    )
    (net (code "62") (name "unconnected-(U1-PA7(ADC7{slash}PCINT7)-Pad30)") (class "Default")
      (node (ref "U1") (pin "30") (pinfunction "PA7(ADC7/PCINT7)_30") (pintype "bidirectional"))
    )
    (net (code "63") (name "unconnected-(U1-PB3(AIN1{slash}OC0A{slash}PCINT11)-Pad43)") (class "Default")
      (node (ref "U1") (pin "43") (pinfunction "PB3(AIN1/OC0A/PCINT11)_43") (pintype "bidirectional"))
    )
    (net (code "64") (name "unconnected-(U1-PC6(TOSC1{slash}PCINT22)-Pad25)") (class "Default")
      (node (ref "U1") (pin "25") (pinfunction "PC6(TOSC1/PCINT22)_25") (pintype "bidirectional"))
    )
    (net (code "65") (name "unconnected-(U1-PC7(TOSC2{slash}PCINT23)-Pad26)") (class "Default")
      (node (ref "U1") (pin "26") (pinfunction "PC7(TOSC2/PCINT23)_26") (pintype "bidirectional"))
    )
    (net (code "66") (name "unconnected-(U2-~{FAULT}-Pad6)") (class "Default")
      (node (ref "U2") (pin "6") (pinfunction "~{FAULT}_6") (pintype "bidirectional"))
    )
  )
)
